# orao_keyboard.net
KiCad netlist of a schematic drawn in EAGLE
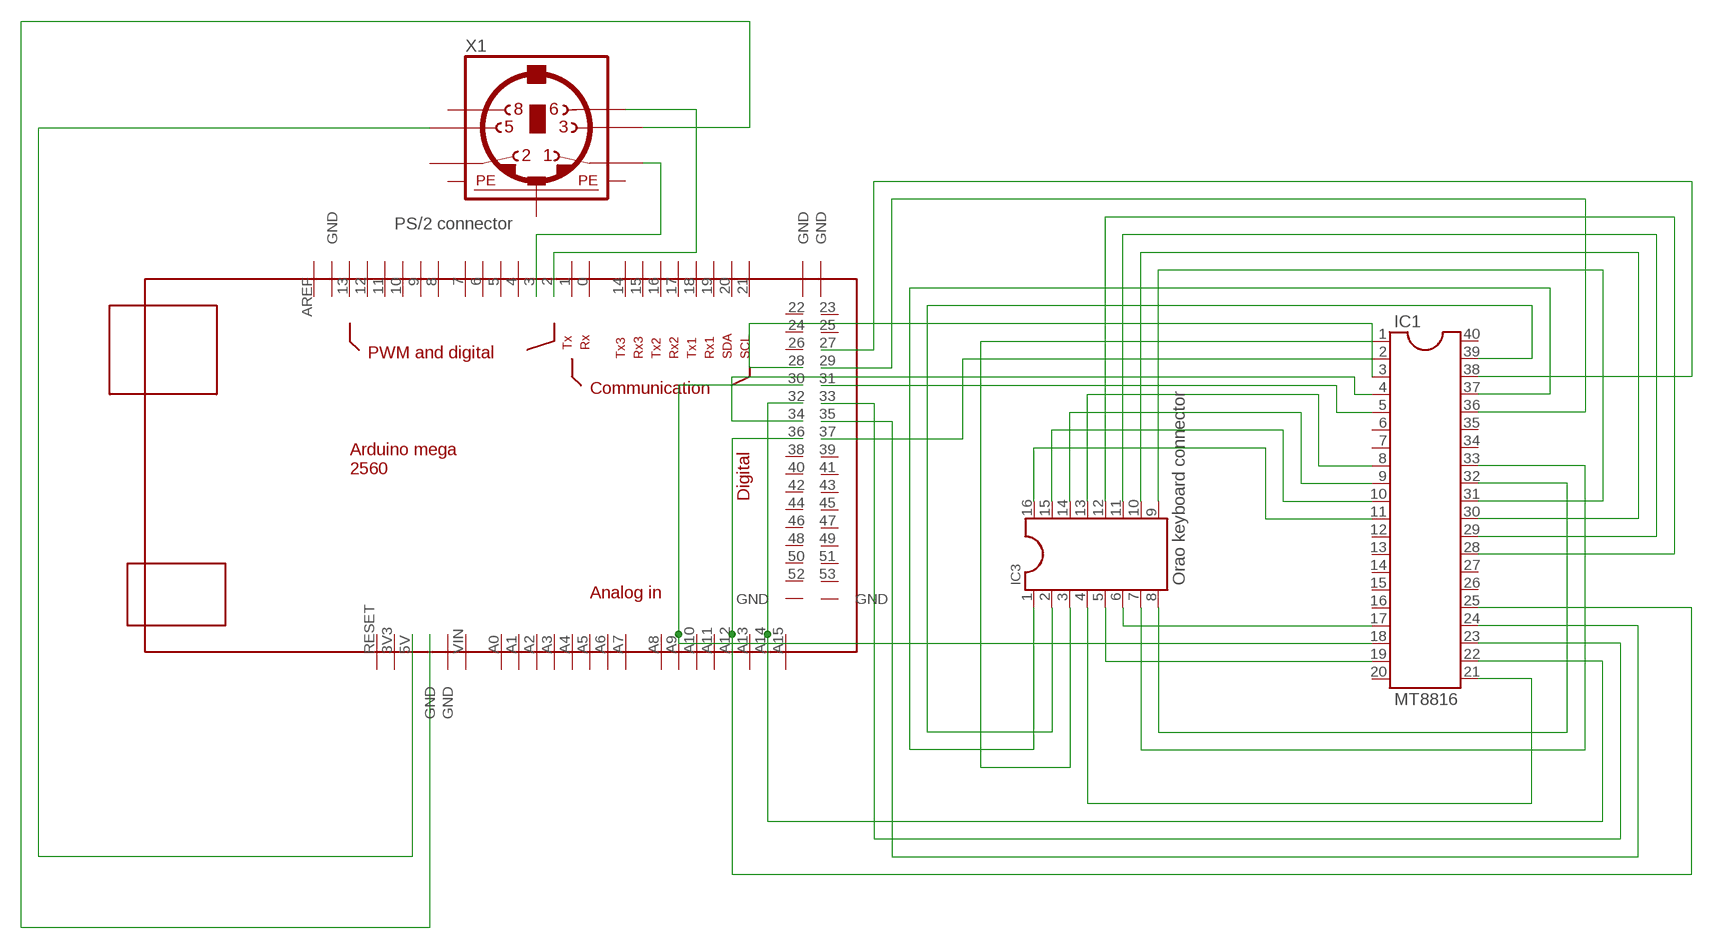
[diagram p0: schematic, sheet 1]

(export (version "E")
  (design (tool "Eeschema 10.0.6"))
  (components
    (comp (ref "IC1")
      (value "MT8816")
      (footprint "eagle-import:DIL40")
      (libsource (lib "eagle-import") (part "DIL40"))
    )
    (comp (ref "IC3")
      (value "Orao keyboard connector")
      (footprint "eagle-import:SOCKED-16")
      (libsource (lib "eagle-import") (part "DIL16S"))
    )
    (comp (ref "U$1")
      (value "MEGA_DEVICE")
      (footprint "eagle-import:MEGAOUTLINE")
      (libsource (lib "eagle-import") (part "MEGA_DEVICE"))
    )
    (comp (ref "X1")
      (value "PS/2 connector")
      (footprint "eagle-import:M_DIN6")
      (libsource (lib "eagle-import") (part "MINI_DIN_6"))
    )
  )
  (nets
    (net (code "1") (name "/PE1") (class "Default")
      (node (ref "X1") (pin "SH1") (pinfunction "PE1_SH1") (pintype "power_in"))
    )
    (net (code "2") (name "/PE2") (class "Default")
      (node (ref "X1") (pin "SH2") (pinfunction "PE2_SH2") (pintype "power_in"))
    )
    (net (code "3") (name "/PE3") (class "Default")
      (node (ref "X1") (pin "SH3") (pinfunction "PE3_SH3") (pintype "power_in"))
    )
    (net (code "4") (name "Net-(IC1-Pad1)") (class "Default")
      (node (ref "IC1") (pin "1") (pinfunction "1_1") (pintype "passive"))
      (node (ref "IC3") (pin "3") (pinfunction "3_3") (pintype "passive"))
    )
    (net (code "5") (name "Net-(IC1-Pad2)") (class "Default")
      (node (ref "IC1") (pin "2") (pinfunction "2_2") (pintype "passive"))
      (node (ref "U$1") (pin "37") (pinfunction "37_37") (pintype "bidirectional"))
    )
    (net (code "6") (name "Net-(IC1-Pad3)") (class "Default")
      (node (ref "IC1") (pin "3") (pinfunction "3_3") (pintype "passive"))
      (node (ref "U$1") (pin "28") (pinfunction "28_28") (pintype "bidirectional"))
    )
    (net (code "7") (name "Net-(IC1-Pad4)") (class "Default")
      (node (ref "IC1") (pin "4") (pinfunction "4_4") (pintype "passive"))
      (node (ref "U$1") (pin "34") (pinfunction "34_34") (pintype "bidirectional"))
    )
    (net (code "8") (name "Net-(IC1-Pad5)") (class "Default")
      (node (ref "IC1") (pin "5") (pinfunction "5_5") (pintype "passive"))
      (node (ref "U$1") (pin "31") (pinfunction "31_31") (pintype "bidirectional"))
    )
    (net (code "9") (name "Net-(IC1-Pad8)") (class "Default")
      (node (ref "IC1") (pin "8") (pinfunction "8_8") (pintype "passive"))
      (node (ref "IC3") (pin "13") (pinfunction "13_13") (pintype "passive"))
    )
    (net (code "10") (name "Net-(IC1-Pad9)") (class "Default")
      (node (ref "IC1") (pin "9") (pinfunction "9_9") (pintype "passive"))
      (node (ref "IC3") (pin "14") (pinfunction "14_14") (pintype "passive"))
    )
    (net (code "11") (name "Net-(IC1-Pad10)") (class "Default")
      (node (ref "IC1") (pin "10") (pinfunction "10_10") (pintype "passive"))
      (node (ref "IC3") (pin "15") (pinfunction "15_15") (pintype "passive"))
    )
    (net (code "12") (name "Net-(IC1-Pad11)") (class "Default")
      (node (ref "IC1") (pin "11") (pinfunction "11_11") (pintype "passive"))
      (node (ref "IC3") (pin "16") (pinfunction "16_16") (pintype "passive"))
    )
    (net (code "13") (name "Net-(IC1-Pad17)") (class "Default")
      (node (ref "IC1") (pin "17") (pinfunction "17_17") (pintype "passive"))
      (node (ref "IC3") (pin "6") (pinfunction "6_6") (pintype "passive"))
    )
    (net (code "14") (name "Net-(IC1-Pad18)") (class "Default")
      (node (ref "IC1") (pin "18") (pinfunction "18_18") (pintype "passive"))
      (node (ref "U$1") (pin "30") (pinfunction "30_30") (pintype "bidirectional"))
      (node (ref "U$1") (pin "A9") (pinfunction "A9_A9") (pintype "bidirectional"))
    )
    (net (code "15") (name "Net-(IC1-Pad19)") (class "Default")
      (node (ref "IC1") (pin "19") (pinfunction "19_19") (pintype "passive"))
      (node (ref "IC3") (pin "5") (pinfunction "5_5") (pintype "passive"))
    )
    (net (code "16") (name "Net-(IC1-Pad21)") (class "Default")
      (node (ref "IC1") (pin "21") (pinfunction "21_21") (pintype "passive"))
      (node (ref "IC3") (pin "4") (pinfunction "4_4") (pintype "passive"))
    )
    (net (code "17") (name "Net-(IC1-Pad22)") (class "Default")
      (node (ref "IC1") (pin "22") (pinfunction "22_22") (pintype "passive"))
      (node (ref "U$1") (pin "32") (pinfunction "32_32") (pintype "bidirectional"))
      (node (ref "U$1") (pin "A14") (pinfunction "A14_A14") (pintype "bidirectional"))
    )
    (net (code "18") (name "Net-(IC1-Pad23)") (class "Default")
      (node (ref "IC1") (pin "23") (pinfunction "23_23") (pintype "passive"))
      (node (ref "U$1") (pin "33") (pinfunction "33_33") (pintype "bidirectional"))
    )
    (net (code "19") (name "Net-(IC1-Pad24)") (class "Default")
      (node (ref "IC1") (pin "24") (pinfunction "24_24") (pintype "passive"))
      (node (ref "U$1") (pin "35") (pinfunction "35_35") (pintype "bidirectional"))
    )
    (net (code "20") (name "Net-(IC1-Pad25)") (class "Default")
      (node (ref "IC1") (pin "25") (pinfunction "25_25") (pintype "passive"))
      (node (ref "U$1") (pin "36") (pinfunction "36_36") (pintype "bidirectional"))
      (node (ref "U$1") (pin "A12") (pinfunction "A12_A12") (pintype "bidirectional"))
    )
    (net (code "21") (name "Net-(IC1-Pad28)") (class "Default")
      (node (ref "IC1") (pin "28") (pinfunction "28_28") (pintype "passive"))
      (node (ref "IC3") (pin "12") (pinfunction "12_12") (pintype "passive"))
    )
    (net (code "22") (name "Net-(IC1-Pad29)") (class "Default")
      (node (ref "IC1") (pin "29") (pinfunction "29_29") (pintype "passive"))
      (node (ref "IC3") (pin "11") (pinfunction "11_11") (pintype "passive"))
    )
    (net (code "23") (name "Net-(IC1-Pad30)") (class "Default")
      (node (ref "IC1") (pin "30") (pinfunction "30_30") (pintype "passive"))
      (node (ref "IC3") (pin "10") (pinfunction "10_10") (pintype "passive"))
    )
    (net (code "24") (name "Net-(IC1-Pad31)") (class "Default")
      (node (ref "IC1") (pin "31") (pinfunction "31_31") (pintype "passive"))
      (node (ref "IC3") (pin "9") (pinfunction "9_9") (pintype "passive"))
    )
    (net (code "25") (name "Net-(IC1-Pad32)") (class "Default")
      (node (ref "IC1") (pin "32") (pinfunction "32_32") (pintype "passive"))
      (node (ref "IC3") (pin "8") (pinfunction "8_8") (pintype "passive"))
    )
    (net (code "26") (name "Net-(IC1-Pad33)") (class "Default")
      (node (ref "IC1") (pin "33") (pinfunction "33_33") (pintype "passive"))
      (node (ref "IC3") (pin "7") (pinfunction "7_7") (pintype "passive"))
    )
    (net (code "27") (name "Net-(IC1-Pad36)") (class "Default")
      (node (ref "IC1") (pin "36") (pinfunction "36_36") (pintype "passive"))
      (node (ref "U$1") (pin "29") (pinfunction "29_29") (pintype "bidirectional"))
    )
    (net (code "28") (name "Net-(IC1-Pad37)") (class "Default")
      (node (ref "IC1") (pin "37") (pinfunction "37_37") (pintype "passive"))
      (node (ref "IC3") (pin "1") (pinfunction "1_1") (pintype "passive"))
    )
    (net (code "29") (name "Net-(IC1-Pad38)") (class "Default")
      (node (ref "IC1") (pin "38") (pinfunction "38_38") (pintype "passive"))
      (node (ref "U$1") (pin "27") (pinfunction "27_27") (pintype "bidirectional"))
    )
    (net (code "30") (name "Net-(IC1-Pad39)") (class "Default")
      (node (ref "IC1") (pin "39") (pinfunction "39_39") (pintype "passive"))
      (node (ref "IC3") (pin "2") (pinfunction "2_2") (pintype "passive"))
    )
    (net (code "31") (name "Net-(U$1-GND-PadGND@2)") (class "Default")
      (node (ref "U$1") (pin "GND@2") (pinfunction "GND_GND@2") (pintype "bidirectional"))
      (node (ref "X1") (pin "3") (pinfunction "3_3") (pintype "passive"))
    )
    (net (code "32") (name "Net-(U$1-Pad2)") (class "Default")
      (node (ref "U$1") (pin "2") (pinfunction "2_2") (pintype "bidirectional"))
      (node (ref "X1") (pin "6") (pinfunction "6_6") (pintype "passive"))
    )
    (net (code "33") (name "Net-(U$1-Pad3)") (class "Default")
      (node (ref "U$1") (pin "3") (pinfunction "3_3") (pintype "bidirectional"))
      (node (ref "X1") (pin "1") (pinfunction "1_1") (pintype "passive"))
    )
    (net (code "34") (name "Net-(U$1-Pad5V)") (class "Default")
      (node (ref "U$1") (pin "5V") (pinfunction "5V_5V") (pintype "bidirectional"))
      (node (ref "X1") (pin "5") (pinfunction "5_5") (pintype "passive"))
    )
    (net (code "35") (name "unconnected-(IC1-Pad6)") (class "Default")
      (node (ref "IC1") (pin "6") (pinfunction "6_6") (pintype "passive"))
    )
    (net (code "36") (name "unconnected-(IC1-Pad7)") (class "Default")
      (node (ref "IC1") (pin "7") (pinfunction "7_7") (pintype "passive"))
    )
    (net (code "37") (name "unconnected-(IC1-Pad12)") (class "Default")
      (node (ref "IC1") (pin "12") (pinfunction "12_12") (pintype "passive"))
    )
    (net (code "38") (name "unconnected-(IC1-Pad13)") (class "Default")
      (node (ref "IC1") (pin "13") (pinfunction "13_13") (pintype "passive"))
    )
    (net (code "39") (name "unconnected-(IC1-Pad14)") (class "Default")
      (node (ref "IC1") (pin "14") (pinfunction "14_14") (pintype "passive"))
    )
    (net (code "40") (name "unconnected-(IC1-Pad15)") (class "Default")
      (node (ref "IC1") (pin "15") (pinfunction "15_15") (pintype "passive"))
    )
    (net (code "41") (name "unconnected-(IC1-Pad16)") (class "Default")
      (node (ref "IC1") (pin "16") (pinfunction "16_16") (pintype "passive"))
    )
    (net (code "42") (name "unconnected-(IC1-Pad20)") (class "Default")
      (node (ref "IC1") (pin "20") (pinfunction "20_20") (pintype "passive"))
    )
    (net (code "43") (name "unconnected-(IC1-Pad26)") (class "Default")
      (node (ref "IC1") (pin "26") (pinfunction "26_26") (pintype "passive"))
    )
    (net (code "44") (name "unconnected-(IC1-Pad27)") (class "Default")
      (node (ref "IC1") (pin "27") (pinfunction "27_27") (pintype "passive"))
    )
    (net (code "45") (name "unconnected-(IC1-Pad34)") (class "Default")
      (node (ref "IC1") (pin "34") (pinfunction "34_34") (pintype "passive"))
    )
    (net (code "46") (name "unconnected-(IC1-Pad35)") (class "Default")
      (node (ref "IC1") (pin "35") (pinfunction "35_35") (pintype "passive"))
    )
    (net (code "47") (name "unconnected-(IC1-Pad40)") (class "Default")
      (node (ref "IC1") (pin "40") (pinfunction "40_40") (pintype "passive"))
    )
    (net (code "48") (name "unconnected-(U$1-GND-PadGND@1)") (class "Default")
      (node (ref "U$1") (pin "GND@1") (pinfunction "GND_GND@1") (pintype "bidirectional"))
    )
    (net (code "49") (name "unconnected-(U$1-GND-PadGND@3)") (class "Default")
      (node (ref "U$1") (pin "GND@3") (pinfunction "GND_GND@3") (pintype "bidirectional"))
    )
    (net (code "50") (name "unconnected-(U$1-GND-PadGND@4)") (class "Default")
      (node (ref "U$1") (pin "GND@4") (pinfunction "GND_GND@4") (pintype "bidirectional"))
    )
    (net (code "51") (name "unconnected-(U$1-GND-PadGND@5)") (class "Default")
      (node (ref "U$1") (pin "GND@5") (pinfunction "GND_GND@5") (pintype "bidirectional"))
    )
    (net (code "52") (name "unconnected-(U$1-GND-PadGND@6)") (class "Default")
      (node (ref "U$1") (pin "GND@6") (pinfunction "GND_GND@6") (pintype "bidirectional"))
    )
    (net (code "53") (name "unconnected-(U$1-GND-PadGND@7)") (class "Default")
      (node (ref "U$1") (pin "GND@7") (pinfunction "GND_GND@7") (pintype "bidirectional"))
    )
    (net (code "54") (name "unconnected-(U$1-Pad0)") (class "Default")
      (node (ref "U$1") (pin "0") (pinfunction "0_0") (pintype "bidirectional"))
    )
    (net (code "55") (name "unconnected-(U$1-Pad1)") (class "Default")
      (node (ref "U$1") (pin "1") (pinfunction "1_1") (pintype "bidirectional"))
    )
    (net (code "56") (name "unconnected-(U$1-Pad3V3)") (class "Default")
      (node (ref "U$1") (pin "3V3") (pinfunction "3V3_3V3") (pintype "bidirectional"))
    )
    (net (code "57") (name "unconnected-(U$1-Pad4)") (class "Default")
      (node (ref "U$1") (pin "4") (pinfunction "4_4") (pintype "bidirectional"))
    )
    (net (code "58") (name "unconnected-(U$1-Pad5)") (class "Default")
      (node (ref "U$1") (pin "5") (pinfunction "5_5") (pintype "bidirectional"))
    )
    (net (code "59") (name "unconnected-(U$1-Pad6)") (class "Default")
      (node (ref "U$1") (pin "6") (pinfunction "6_6") (pintype "bidirectional"))
    )
    (net (code "60") (name "unconnected-(U$1-Pad7)") (class "Default")
      (node (ref "U$1") (pin "7") (pinfunction "7_7") (pintype "bidirectional"))
    )
    (net (code "61") (name "unconnected-(U$1-Pad8)") (class "Default")
      (node (ref "U$1") (pin "8") (pinfunction "8_8") (pintype "bidirectional"))
    )
    (net (code "62") (name "unconnected-(U$1-Pad9)") (class "Default")
      (node (ref "U$1") (pin "9") (pinfunction "9_9") (pintype "bidirectional"))
    )
    (net (code "63") (name "unconnected-(U$1-Pad10)") (class "Default")
      (node (ref "U$1") (pin "10") (pinfunction "10_10") (pintype "bidirectional"))
    )
    (net (code "64") (name "unconnected-(U$1-Pad11)") (class "Default")
      (node (ref "U$1") (pin "11") (pinfunction "11_11") (pintype "bidirectional"))
    )
    (net (code "65") (name "unconnected-(U$1-Pad12)") (class "Default")
      (node (ref "U$1") (pin "12") (pinfunction "12_12") (pintype "bidirectional"))
    )
    (net (code "66") (name "unconnected-(U$1-Pad13)") (class "Default")
      (node (ref "U$1") (pin "13") (pinfunction "13_13") (pintype "bidirectional"))
    )
    (net (code "67") (name "unconnected-(U$1-Pad14)") (class "Default")
      (node (ref "U$1") (pin "14") (pinfunction "14_14") (pintype "bidirectional"))
    )
    (net (code "68") (name "unconnected-(U$1-Pad15)") (class "Default")
      (node (ref "U$1") (pin "15") (pinfunction "15_15") (pintype "bidirectional"))
    )
    (net (code "69") (name "unconnected-(U$1-Pad16)") (class "Default")
      (node (ref "U$1") (pin "16") (pinfunction "16_16") (pintype "bidirectional"))
    )
    (net (code "70") (name "unconnected-(U$1-Pad17)") (class "Default")
      (node (ref "U$1") (pin "17") (pinfunction "17_17") (pintype "bidirectional"))
    )
    (net (code "71") (name "unconnected-(U$1-Pad18)") (class "Default")
      (node (ref "U$1") (pin "18") (pinfunction "18_18") (pintype "bidirectional"))
    )
    (net (code "72") (name "unconnected-(U$1-Pad19)") (class "Default")
      (node (ref "U$1") (pin "19") (pinfunction "19_19") (pintype "bidirectional"))
    )
    (net (code "73") (name "unconnected-(U$1-Pad20)") (class "Default")
      (node (ref "U$1") (pin "20") (pinfunction "20_20") (pintype "bidirectional"))
    )
    (net (code "74") (name "unconnected-(U$1-Pad21)") (class "Default")
      (node (ref "U$1") (pin "21") (pinfunction "21_21") (pintype "bidirectional"))
    )
    (net (code "75") (name "unconnected-(U$1-Pad22)") (class "Default")
      (node (ref "U$1") (pin "22") (pinfunction "22_22") (pintype "bidirectional"))
    )
    (net (code "76") (name "unconnected-(U$1-Pad23)") (class "Default")
      (node (ref "U$1") (pin "23") (pinfunction "23_23") (pintype "bidirectional"))
    )
    (net (code "77") (name "unconnected-(U$1-Pad24)") (class "Default")
      (node (ref "U$1") (pin "24") (pinfunction "24_24") (pintype "bidirectional"))
    )
    (net (code "78") (name "unconnected-(U$1-Pad25)") (class "Default")
      (node (ref "U$1") (pin "25") (pinfunction "25_25") (pintype "bidirectional"))
    )
    (net (code "79") (name "unconnected-(U$1-Pad26)") (class "Default")
      (node (ref "U$1") (pin "26") (pinfunction "26_26") (pintype "bidirectional"))
    )
    (net (code "80") (name "unconnected-(U$1-Pad38)") (class "Default")
      (node (ref "U$1") (pin "38") (pinfunction "38_38") (pintype "bidirectional"))
    )
    (net (code "81") (name "unconnected-(U$1-Pad39)") (class "Default")
      (node (ref "U$1") (pin "39") (pinfunction "39_39") (pintype "bidirectional"))
    )
    (net (code "82") (name "unconnected-(U$1-Pad40)") (class "Default")
      (node (ref "U$1") (pin "40") (pinfunction "40_40") (pintype "bidirectional"))
    )
    (net (code "83") (name "unconnected-(U$1-Pad41)") (class "Default")
      (node (ref "U$1") (pin "41") (pinfunction "41_41") (pintype "bidirectional"))
    )
    (net (code "84") (name "unconnected-(U$1-Pad42)") (class "Default")
      (node (ref "U$1") (pin "42") (pinfunction "42_42") (pintype "bidirectional"))
    )
    (net (code "85") (name "unconnected-(U$1-Pad43)") (class "Default")
      (node (ref "U$1") (pin "43") (pinfunction "43_43") (pintype "bidirectional"))
    )
    (net (code "86") (name "unconnected-(U$1-Pad44)") (class "Default")
      (node (ref "U$1") (pin "44") (pinfunction "44_44") (pintype "bidirectional"))
    )
    (net (code "87") (name "unconnected-(U$1-Pad45)") (class "Default")
      (node (ref "U$1") (pin "45") (pinfunction "45_45") (pintype "bidirectional"))
    )
    (net (code "88") (name "unconnected-(U$1-Pad46)") (class "Default")
      (node (ref "U$1") (pin "46") (pinfunction "46_46") (pintype "bidirectional"))
    )
    (net (code "89") (name "unconnected-(U$1-Pad47)") (class "Default")
      (node (ref "U$1") (pin "47") (pinfunction "47_47") (pintype "bidirectional"))
    )
    (net (code "90") (name "unconnected-(U$1-Pad48)") (class "Default")
      (node (ref "U$1") (pin "48") (pinfunction "48_48") (pintype "bidirectional"))
    )
    (net (code "91") (name "unconnected-(U$1-Pad49)") (class "Default")
      (node (ref "U$1") (pin "49") (pinfunction "49_49") (pintype "bidirectional"))
    )
    (net (code "92") (name "unconnected-(U$1-Pad50)") (class "Default")
      (node (ref "U$1") (pin "50") (pinfunction "50_50") (pintype "bidirectional"))
    )
    (net (code "93") (name "unconnected-(U$1-Pad51)") (class "Default")
      (node (ref "U$1") (pin "51") (pinfunction "51_51") (pintype "bidirectional"))
    )
    (net (code "94") (name "unconnected-(U$1-Pad52)") (class "Default")
      (node (ref "U$1") (pin "52") (pinfunction "52_52") (pintype "bidirectional"))
    )
    (net (code "95") (name "unconnected-(U$1-Pad53)") (class "Default")
      (node (ref "U$1") (pin "53") (pinfunction "53_53") (pintype "bidirectional"))
    )
    (net (code "96") (name "unconnected-(U$1-PadA0)") (class "Default")
      (node (ref "U$1") (pin "A0") (pinfunction "A0_A0") (pintype "bidirectional"))
    )
    (net (code "97") (name "unconnected-(U$1-PadA1)") (class "Default")
      (node (ref "U$1") (pin "A1") (pinfunction "A1_A1") (pintype "bidirectional"))
    )
    (net (code "98") (name "unconnected-(U$1-PadA2)") (class "Default")
      (node (ref "U$1") (pin "A2") (pinfunction "A2_A2") (pintype "bidirectional"))
    )
    (net (code "99") (name "unconnected-(U$1-PadA3)") (class "Default")
      (node (ref "U$1") (pin "A3") (pinfunction "A3_A3") (pintype "bidirectional"))
    )
    (net (code "100") (name "unconnected-(U$1-PadA4)") (class "Default")
      (node (ref "U$1") (pin "A4") (pinfunction "A4_A4") (pintype "bidirectional"))
    )
    (net (code "101") (name "unconnected-(U$1-PadA5)") (class "Default")
      (node (ref "U$1") (pin "A5") (pinfunction "A5_A5") (pintype "bidirectional"))
    )
    (net (code "102") (name "unconnected-(U$1-PadA6)") (class "Default")
      (node (ref "U$1") (pin "A6") (pinfunction "A6_A6") (pintype "bidirectional"))
    )
    (net (code "103") (name "unconnected-(U$1-PadA7)") (class "Default")
      (node (ref "U$1") (pin "A7") (pinfunction "A7_A7") (pintype "bidirectional"))
    )
    (net (code "104") (name "unconnected-(U$1-PadA8)") (class "Default")
      (node (ref "U$1") (pin "A8") (pinfunction "A8_A8") (pintype "bidirectional"))
    )
    (net (code "105") (name "unconnected-(U$1-PadA10)") (class "Default")
      (node (ref "U$1") (pin "A10") (pinfunction "A10_A10") (pintype "bidirectional"))
    )
    (net (code "106") (name "unconnected-(U$1-PadA11)") (class "Default")
      (node (ref "U$1") (pin "A11") (pinfunction "A11_A11") (pintype "bidirectional"))
    )
    (net (code "107") (name "unconnected-(U$1-PadA13)") (class "Default")
      (node (ref "U$1") (pin "A13") (pinfunction "A13_A13") (pintype "bidirectional"))
    )
    (net (code "108") (name "unconnected-(U$1-PadA15)") (class "Default")
      (node (ref "U$1") (pin "A15") (pinfunction "A15_A15") (pintype "bidirectional"))
    )
    (net (code "109") (name "unconnected-(U$1-PadAREF)") (class "Default")
      (node (ref "U$1") (pin "AREF") (pinfunction "AREF_AREF") (pintype "bidirectional"))
    )
    (net (code "110") (name "unconnected-(U$1-PadRESET)") (class "Default")
      (node (ref "U$1") (pin "RESET") (pinfunction "RESET_RESET") (pintype "bidirectional"))
    )
    (net (code "111") (name "unconnected-(U$1-PadVIN)") (class "Default")
      (node (ref "U$1") (pin "VIN") (pinfunction "VIN_VIN") (pintype "bidirectional"))
    )
    (net (code "112") (name "unconnected-(X1-Pad2)") (class "Default")
      (node (ref "X1") (pin "2") (pinfunction "2_2") (pintype "passive"))
    )
    (net (code "113") (name "unconnected-(X1-Pad8)") (class "Default")
      (node (ref "X1") (pin "8") (pinfunction "8_8") (pintype "passive"))
    )
  )
)
